# Single_PCB_-_PSK-10D-5.net
KiCad netlist of a schematic drawn in EAGLE
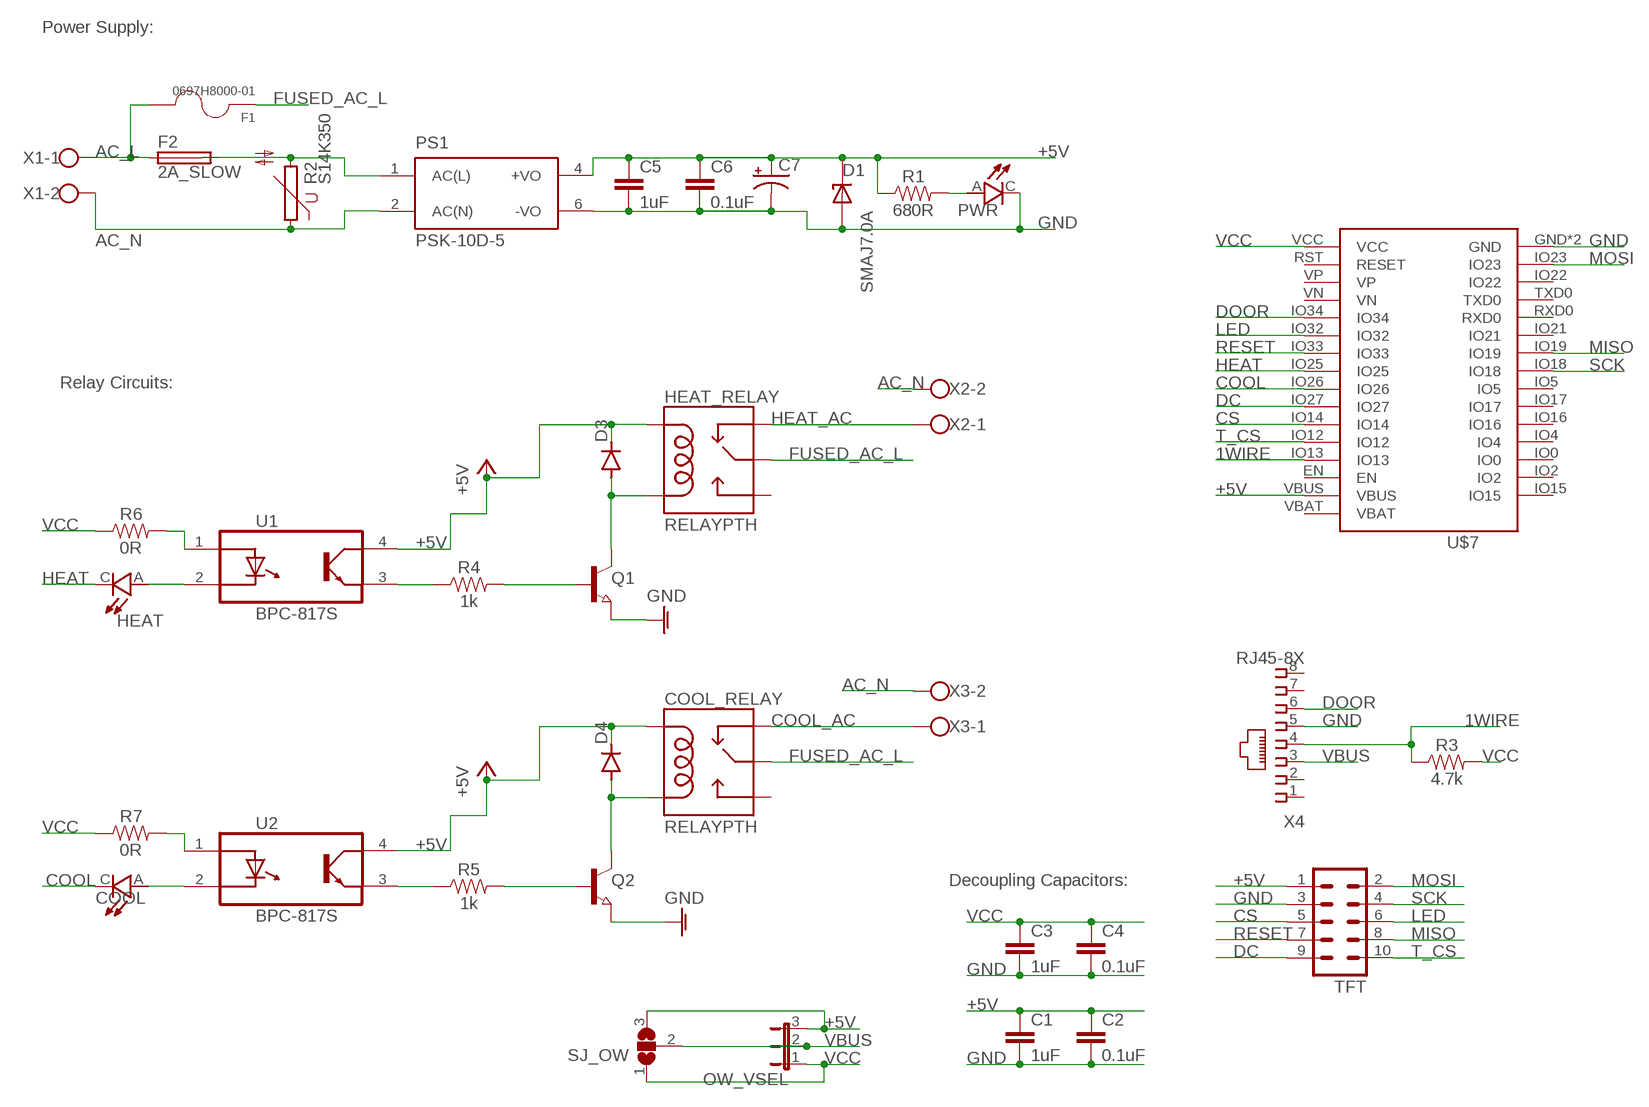
[diagram p0: schematic, sheet 1]

(export (version "E")
  (design (tool "Eeschema 10.0.6"))
  (components
    (comp (ref "C1")
      (value "1uF")
      (footprint "eagle-import:SMD-0805")
      (fields (field (name "LCSC_PART") "C28323"))
      (libsource (lib "eagle-import") (part "CAP_SMD0805"))
    )
    (comp (ref "C2")
      (value "0.1uF")
      (footprint "eagle-import:SMD-0805")
      (fields (field (name "LCSC_PART") "C49678"))
      (libsource (lib "eagle-import") (part "CAP_SMD0805"))
    )
    (comp (ref "C3")
      (value "1uF")
      (footprint "eagle-import:SMD-0805")
      (fields (field (name "LCSC_PART") "C28323"))
      (libsource (lib "eagle-import") (part "CAP_SMD0805"))
    )
    (comp (ref "C4")
      (value "0.1uF")
      (footprint "eagle-import:SMD-0805")
      (fields (field (name "LCSC_PART") "C49678"))
      (libsource (lib "eagle-import") (part "CAP_SMD0805"))
    )
    (comp (ref "C5")
      (value "1uF")
      (footprint "eagle-import:SMD-0805")
      (fields (field (name "LCSC_PART") "C28323"))
      (libsource (lib "eagle-import") (part "CAP_SMD0805"))
    )
    (comp (ref "C6")
      (value "0.1uF")
      (footprint "eagle-import:SMD-0805")
      (fields (field (name "LCSC_PART") "C49678"))
      (libsource (lib "eagle-import") (part "CAP_SMD0805"))
    )
    (comp (ref "C7")
      (value "220uF")
      (footprint "eagle-import:CAPPRD750W80D1600H2700")
      (fields (field (name "LCSC_PART") "C43349"))
      (libsource (lib "eagle-import") (part "220UF-POLAR220UF"))
    )
    (comp (ref "COOL")
      (value "LED_0603LED_SMD_0603")
      (footprint "eagle-import:LED_SMD_0603")
      (fields (field (name "LCSC_PART") "C2286") (field (name "LCSC_PART_1") "C2286"))
      (libsource (lib "eagle-import") (part "LED_0603LED_SMD_0603"))
    )
    (comp (ref "COOL_RELAY")
      (value "RELAYPTH")
      (footprint "eagle-import:SRD-05VDC-SL-C")
      (fields (field (name "LCSC_PART") "C35449"))
      (libsource (lib "eagle-import") (part "RELAYPTH"))
    )
    (comp (ref "D1")
      (value "SMAJ7.0A")
      (footprint "eagle-import:DIOM4325X250N")
      (fields (field (name "MF") "Littelfuse") (field (name "LCSC_PART") "C309904"))
      (libsource (lib "eagle-import") (part "SMAJ7.0A"))
    )
    (comp (ref "D3")
      (value "DIODE-DO214AC")
      (footprint "eagle-import:DO214AC")
      (fields (field (name "LCSC_PART") "C95872"))
      (libsource (lib "eagle-import") (part "DIODE-DO214AC"))
    )
    (comp (ref "D4")
      (value "DIODE-DO214AC")
      (footprint "eagle-import:DO214AC")
      (fields (field (name "LCSC_PART") "C95872"))
      (libsource (lib "eagle-import") (part "DIODE-DO214AC"))
    )
    (comp (ref "F1")
      (value "0697H8000-01")
      (footprint "eagle-import:FUSRR508W60L835T400H810")
      (fields (field (name "MF") "Bel Fuse"))
      (libsource (lib "eagle-import") (part "0697H8000-01"))
    )
    (comp (ref "F2")
      (value "2A_SLOW")
      (footprint "eagle-import:FUSE_BK_PCE-5-R")
      (libsource (lib "eagle-import") (part "FUSEFUSE_85_43"))
    )
    (comp (ref "HEAT")
      (value "LED_0603LED_SMD_0603")
      (footprint "eagle-import:LED_SMD_0603")
      (fields (field (name "LCSC_PART") "C2286") (field (name "LCSC_PART_1") "C2286"))
      (libsource (lib "eagle-import") (part "LED_0603LED_SMD_0603"))
    )
    (comp (ref "HEAT_RELAY")
      (value "RELAYPTH")
      (footprint "eagle-import:SRD-05VDC-SL-C")
      (fields (field (name "LCSC_PART") "C35449"))
      (libsource (lib "eagle-import") (part "RELAYPTH"))
    )
    (comp (ref "OW_VSEL")
      (value "JP2ENOLABEL")
      (footprint "eagle-import:JP2-NOLABEL")
      (libsource (lib "eagle-import") (part "JP2ENOLABEL"))
    )
    (comp (ref "PS1")
      (value "PSK-10D-5")
      (footprint "eagle-import:CONV_PSK-10D-5")
      (fields (field (name "MF") "CUI"))
      (libsource (lib "eagle-import") (part "PSK-10D-5"))
    )
    (comp (ref "PWR")
      (value "LED_0603LED_SMD_0603")
      (footprint "eagle-import:LED_SMD_0603")
      (fields (field (name "LCSC_PART") "C2286") (field (name "LCSC_PART_1") "C2286"))
      (libsource (lib "eagle-import") (part "LED_0603LED_SMD_0603"))
    )
    (comp (ref "Q1")
      (value "NPN-TRANSISTOR_SOT23")
      (footprint "eagle-import:SOT23")
      (libsource (lib "eagle-import") (part "NPN-TRANSISTOR_SOT23"))
    )
    (comp (ref "Q2")
      (value "NPN-TRANSISTOR_SOT23")
      (footprint "eagle-import:SOT23")
      (libsource (lib "eagle-import") (part "NPN-TRANSISTOR_SOT23"))
    )
    (comp (ref "R1")
      (value "680R")
      (footprint "eagle-import:SMD-0805")
      (fields (field (name "LCSC_PART") "C17798"))
      (libsource (lib "eagle-import") (part "RES_SMD0805"))
    )
    (comp (ref "R2")
      (value "S14K350")
      (footprint "eagle-import:S10K350")
      (fields (field (name "LCSC_PART") "C78355"))
      (libsource (lib "eagle-import") (part "S10K350"))
    )
    (comp (ref "R3")
      (value "4.7k")
      (footprint "eagle-import:SMD-0805")
      (fields (field (name "LCSC_PART") "C17673"))
      (libsource (lib "eagle-import") (part "RES_SMD0805"))
    )
    (comp (ref "R4")
      (value "1k")
      (footprint "eagle-import:SMD-0805")
      (fields (field (name "LCSC_PART") "C17513"))
      (libsource (lib "eagle-import") (part "RES_SMD0805"))
    )
    (comp (ref "R5")
      (value "1k")
      (footprint "eagle-import:SMD-0805")
      (fields (field (name "LCSC_PART") "C17513"))
      (libsource (lib "eagle-import") (part "RES_SMD0805"))
    )
    (comp (ref "R6")
      (value "0R")
      (footprint "eagle-import:SMD-0805")
      (fields (field (name "LCSC_PART") "C17477"))
      (libsource (lib "eagle-import") (part "RES_SMD0805"))
    )
    (comp (ref "R7")
      (value "0R")
      (footprint "eagle-import:SMD-0805")
      (fields (field (name "LCSC_PART") "C17477"))
      (libsource (lib "eagle-import") (part "RES_SMD0805"))
    )
    (comp (ref "SJ_OW")
      (value "SJ2W")
      (footprint "eagle-import:SJ_2")
      (libsource (lib "eagle-import") (part "SJ2W"))
    )
    (comp (ref "TFT")
      (value "MA05-2")
      (footprint "eagle-import:MA05-2")
      (libsource (lib "eagle-import") (part "MA05-2"))
    )
    (comp (ref "U$7")
      (value "WEMOS-D32D32_PRO_NO-KEEPOUT")
      (footprint "eagle-import:D32_PRO_NO-KEEPOUT")
      (libsource (lib "eagle-import") (part "WEMOS-D32D32_PRO_NO-KEEPOUT"))
    )
    (comp (ref "U1")
      (value "BPC-817S")
      (footprint "eagle-import:SOIC127P700X210-4N")
      (fields (field (name "LCSC_PART") "C106900"))
      (libsource (lib "eagle-import") (part "BPC-817S"))
    )
    (comp (ref "U2")
      (value "BPC-817S")
      (footprint "eagle-import:SOIC127P700X210-4N")
      (fields (field (name "LCSC_PART") "C106900"))
      (libsource (lib "eagle-import") (part "BPC-817S"))
    )
    (comp (ref "X1")
      (value "W237-102")
      (footprint "eagle-import:W237-102")
      (fields (field (name "MPN") "237-102"))
      (libsource (lib "eagle-import") (part "W237-102"))
    )
    (comp (ref "X2")
      (value "W237-102")
      (footprint "eagle-import:W237-102")
      (fields (field (name "MPN") "237-102"))
      (libsource (lib "eagle-import") (part "W237-102"))
    )
    (comp (ref "X3")
      (value "W237-102")
      (footprint "eagle-import:W237-102")
      (fields (field (name "MPN") "237-102"))
      (libsource (lib "eagle-import") (part "W237-102"))
    )
    (comp (ref "X4")
      (value "RJ45-8X")
      (footprint "eagle-import:RJ45-NO-SHIELD")
      (fields (field (name "LCSC_PART") "C3000197"))
      (libsource (lib "eagle-import") (part "RJ45-8X"))
    )
  )
  (nets
    (net (code "1") (name "+5V") (class "Default")
      (node (ref "C1") (pin "1") (pinfunction "1_1") (pintype "passive"))
      (node (ref "C2") (pin "1") (pinfunction "1_1") (pintype "passive"))
      (node (ref "C5") (pin "1") (pinfunction "1_1") (pintype "passive"))
      (node (ref "C6") (pin "1") (pinfunction "1_1") (pintype "passive"))
      (node (ref "C7") (pin "2") (pinfunction "+_2") (pintype "passive"))
      (node (ref "COOL_RELAY") (pin "COIL1") (pinfunction "COIL1_COIL1") (pintype "bidirectional"))
      (node (ref "D1") (pin "C") (pinfunction "C_C") (pintype "passive"))
      (node (ref "D3") (pin "C") (pinfunction "C_C") (pintype "passive"))
      (node (ref "D4") (pin "C") (pinfunction "C_C") (pintype "passive"))
      (node (ref "HEAT_RELAY") (pin "COIL1") (pinfunction "COIL1_COIL1") (pintype "bidirectional"))
      (node (ref "OW_VSEL") (pin "3") (pinfunction "3_3") (pintype "passive"))
      (node (ref "PS1") (pin "4") (pinfunction "+VO_4") (pintype "output"))
      (node (ref "R1") (pin "1") (pinfunction "1_1") (pintype "passive"))
      (node (ref "SJ_OW") (pin "3") (pinfunction "3_3") (pintype "passive"))
      (node (ref "TFT") (pin "1") (pinfunction "1_1") (pintype "passive"))
      (node (ref "U$7") (pin "VBUS") (pinfunction "VBUS_VBUS") (pintype "bidirectional"))
      (node (ref "U1") (pin "4") (pinfunction "CO_4") (pintype "passive"))
      (node (ref "U2") (pin "4") (pinfunction "CO_4") (pintype "passive"))
    )
    (net (code "2") (name "/1WIRE") (class "Default")
      (node (ref "R3") (pin "1") (pinfunction "1_1") (pintype "passive"))
      (node (ref "U$7") (pin "IO13") (pinfunction "IO13_IO13") (pintype "bidirectional"))
      (node (ref "X4") (pin "4") (pinfunction "4_4") (pintype "passive"))
    )
    (net (code "3") (name "/AC_L") (class "Default")
      (node (ref "F1") (pin "2") (pinfunction "2_2") (pintype "passive"))
      (node (ref "F2") (pin "1") (pinfunction "1_1") (pintype "passive"))
      (node (ref "X1") (pin "1") (pinfunction "KL_1") (pintype "passive"))
    )
    (net (code "4") (name "/AC_N") (class "Default")
      (node (ref "PS1") (pin "2") (pinfunction "AC(N)_2") (pintype "input"))
      (node (ref "R2") (pin "1") (pinfunction "1_1") (pintype "passive"))
      (node (ref "X1") (pin "2") (pinfunction "KL_2") (pintype "passive"))
      (node (ref "X2") (pin "2") (pinfunction "KL_2") (pintype "passive"))
      (node (ref "X3") (pin "2") (pinfunction "KL_2") (pintype "passive"))
    )
    (net (code "5") (name "/COOL") (class "Default")
      (node (ref "COOL") (pin "C") (pinfunction "C_C") (pintype "passive"))
      (node (ref "U$7") (pin "IO26") (pinfunction "IO26_IO26") (pintype "bidirectional"))
    )
    (net (code "6") (name "/COOL_AC") (class "Default")
      (node (ref "COOL_RELAY") (pin "SWCLOSED") (pinfunction "SWCLOSE_SWCLOSED") (pintype "bidirectional"))
      (node (ref "X3") (pin "1") (pinfunction "KL_1") (pintype "passive"))
    )
    (net (code "7") (name "/CS") (class "Default")
      (node (ref "TFT") (pin "5") (pinfunction "5_5") (pintype "passive"))
      (node (ref "U$7") (pin "IO14") (pinfunction "IO14_IO14") (pintype "bidirectional"))
    )
    (net (code "8") (name "/DC") (class "Default")
      (node (ref "TFT") (pin "9") (pinfunction "9_9") (pintype "passive"))
      (node (ref "U$7") (pin "IO27") (pinfunction "IO27_IO27") (pintype "bidirectional"))
    )
    (net (code "9") (name "/DOOR") (class "Default")
      (node (ref "U$7") (pin "IO34") (pinfunction "IO34_IO34") (pintype "bidirectional"))
      (node (ref "X4") (pin "6") (pinfunction "6_6") (pintype "passive"))
    )
    (net (code "10") (name "/FUSED_AC_L") (class "Default")
      (node (ref "COOL_RELAY") (pin "SWCOMMON") (pinfunction "SWCOMMON_SWCOMMON") (pintype "bidirectional"))
      (node (ref "F1") (pin "1") (pinfunction "1_1") (pintype "passive"))
      (node (ref "HEAT_RELAY") (pin "SWCOMMON") (pinfunction "SWCOMMON_SWCOMMON") (pintype "bidirectional"))
    )
    (net (code "11") (name "/HEAT") (class "Default")
      (node (ref "HEAT") (pin "C") (pinfunction "C_C") (pintype "passive"))
      (node (ref "U$7") (pin "IO25") (pinfunction "IO25_IO25") (pintype "bidirectional"))
    )
    (net (code "12") (name "/HEAT_AC") (class "Default")
      (node (ref "HEAT_RELAY") (pin "SWCLOSED") (pinfunction "SWCLOSE_SWCLOSED") (pintype "bidirectional"))
      (node (ref "X2") (pin "1") (pinfunction "KL_1") (pintype "passive"))
    )
    (net (code "13") (name "/LED") (class "Default")
      (node (ref "TFT") (pin "6") (pinfunction "6_6") (pintype "passive"))
      (node (ref "U$7") (pin "IO32") (pinfunction "IO32_IO32") (pintype "bidirectional"))
    )
    (net (code "14") (name "/MISO") (class "Default")
      (node (ref "TFT") (pin "8") (pinfunction "8_8") (pintype "passive"))
      (node (ref "U$7") (pin "IO19") (pinfunction "IO19_IO19") (pintype "bidirectional"))
    )
    (net (code "15") (name "/MOSI") (class "Default")
      (node (ref "TFT") (pin "2") (pinfunction "2_2") (pintype "passive"))
      (node (ref "U$7") (pin "IO23") (pinfunction "IO23_IO23") (pintype "bidirectional"))
    )
    (net (code "16") (name "/RESET") (class "Default")
      (node (ref "TFT") (pin "7") (pinfunction "7_7") (pintype "passive"))
      (node (ref "U$7") (pin "IO33") (pinfunction "IO33_IO33") (pintype "bidirectional"))
    )
    (net (code "17") (name "/SCK") (class "Default")
      (node (ref "TFT") (pin "4") (pinfunction "4_4") (pintype "passive"))
      (node (ref "U$7") (pin "IO18") (pinfunction "IO18_IO18") (pintype "bidirectional"))
    )
    (net (code "18") (name "/T_CS") (class "Default")
      (node (ref "TFT") (pin "10") (pinfunction "10_10") (pintype "passive"))
      (node (ref "U$7") (pin "IO12") (pinfunction "IO12_IO12") (pintype "bidirectional"))
    )
    (net (code "19") (name "/VBUS") (class "Default")
      (node (ref "OW_VSEL") (pin "2") (pinfunction "2_2") (pintype "passive"))
      (node (ref "SJ_OW") (pin "2") (pinfunction "2_2") (pintype "passive"))
      (node (ref "X4") (pin "3") (pinfunction "3_3") (pintype "passive"))
    )
    (net (code "20") (name "/VCC") (class "Default")
      (node (ref "C3") (pin "1") (pinfunction "1_1") (pintype "passive"))
      (node (ref "C4") (pin "1") (pinfunction "1_1") (pintype "passive"))
      (node (ref "OW_VSEL") (pin "1") (pinfunction "1_1") (pintype "passive"))
      (node (ref "R3") (pin "2") (pinfunction "2_2") (pintype "passive"))
      (node (ref "R6") (pin "1") (pinfunction "1_1") (pintype "passive"))
      (node (ref "R7") (pin "1") (pinfunction "1_1") (pintype "passive"))
      (node (ref "SJ_OW") (pin "1") (pinfunction "1_1") (pintype "passive"))
      (node (ref "U$7") (pin "VCC") (pinfunction "VCC_VCC") (pintype "power_in"))
    )
    (net (code "21") (name "GNDA") (class "Default")
      (node (ref "C1") (pin "2") (pinfunction "2_2") (pintype "passive"))
      (node (ref "C2") (pin "2") (pinfunction "2_2") (pintype "passive"))
      (node (ref "C3") (pin "2") (pinfunction "2_2") (pintype "passive"))
      (node (ref "C4") (pin "2") (pinfunction "2_2") (pintype "passive"))
      (node (ref "C5") (pin "2") (pinfunction "2_2") (pintype "passive"))
      (node (ref "C6") (pin "2") (pinfunction "2_2") (pintype "passive"))
      (node (ref "C7") (pin "1") (pinfunction "-_1") (pintype "passive"))
      (node (ref "D1") (pin "A") (pinfunction "A_A") (pintype "passive"))
      (node (ref "PS1") (pin "6") (pinfunction "-VO_6") (pintype "output"))
      (node (ref "PWR") (pin "C") (pinfunction "C_C") (pintype "passive"))
      (node (ref "Q1") (pin "2") (pinfunction "E_2") (pintype "passive"))
      (node (ref "Q2") (pin "2") (pinfunction "E_2") (pintype "passive"))
      (node (ref "TFT") (pin "3") (pinfunction "3_3") (pintype "passive"))
      (node (ref "U$7") (pin "GND") (pinfunction "GND_GND") (pintype "power_in"))
      (node (ref "U$7") (pin "GND2") (pinfunction "GND_GND2") (pintype "power_in"))
      (node (ref "X4") (pin "5") (pinfunction "5_5") (pintype "passive"))
    )
    (net (code "22") (name "Net-(PS1-AC(L))") (class "Default")
      (node (ref "F2") (pin "2") (pinfunction "2_2") (pintype "passive"))
      (node (ref "PS1") (pin "1") (pinfunction "AC(L)_1") (pintype "input"))
      (node (ref "R2") (pin "2") (pinfunction "2_2") (pintype "passive"))
    )
    (net (code "23") (name "Net-(PWR-PadA)") (class "Default")
      (node (ref "PWR") (pin "A") (pinfunction "A_A") (pintype "passive"))
      (node (ref "R1") (pin "2") (pinfunction "2_2") (pintype "passive"))
    )
    (net (code "24") (name "Net-(Q1-B)") (class "Default")
      (node (ref "Q1") (pin "1") (pinfunction "B_1") (pintype "passive"))
      (node (ref "R4") (pin "2") (pinfunction "2_2") (pintype "passive"))
    )
    (net (code "25") (name "Net-(Q1-C)") (class "Default")
      (node (ref "D3") (pin "A") (pinfunction "A_A") (pintype "passive"))
      (node (ref "HEAT_RELAY") (pin "COIL0") (pinfunction "COIL0_COIL0") (pintype "bidirectional"))
      (node (ref "Q1") (pin "3") (pinfunction "C_3") (pintype "passive"))
    )
    (net (code "26") (name "Net-(Q2-B)") (class "Default")
      (node (ref "Q2") (pin "1") (pinfunction "B_1") (pintype "passive"))
      (node (ref "R5") (pin "2") (pinfunction "2_2") (pintype "passive"))
    )
    (net (code "27") (name "Net-(Q2-C)") (class "Default")
      (node (ref "COOL_RELAY") (pin "COIL0") (pinfunction "COIL0_COIL0") (pintype "bidirectional"))
      (node (ref "D4") (pin "A") (pinfunction "A_A") (pintype "passive"))
      (node (ref "Q2") (pin "3") (pinfunction "C_3") (pintype "passive"))
    )
    (net (code "28") (name "Net-(U1-A)") (class "Default")
      (node (ref "R6") (pin "2") (pinfunction "2_2") (pintype "passive"))
      (node (ref "U1") (pin "1") (pinfunction "A_1") (pintype "passive"))
    )
    (net (code "29") (name "Net-(U1-C)") (class "Default")
      (node (ref "HEAT") (pin "A") (pinfunction "A_A") (pintype "passive"))
      (node (ref "U1") (pin "2") (pinfunction "C_2") (pintype "passive"))
    )
    (net (code "30") (name "Net-(U1-E)") (class "Default")
      (node (ref "R4") (pin "1") (pinfunction "1_1") (pintype "passive"))
      (node (ref "U1") (pin "3") (pinfunction "E_3") (pintype "passive"))
    )
    (net (code "31") (name "Net-(U2-A)") (class "Default")
      (node (ref "R7") (pin "2") (pinfunction "2_2") (pintype "passive"))
      (node (ref "U2") (pin "1") (pinfunction "A_1") (pintype "passive"))
    )
    (net (code "32") (name "Net-(U2-C)") (class "Default")
      (node (ref "COOL") (pin "A") (pinfunction "A_A") (pintype "passive"))
      (node (ref "U2") (pin "2") (pinfunction "C_2") (pintype "passive"))
    )
    (net (code "33") (name "Net-(U2-E)") (class "Default")
      (node (ref "R5") (pin "1") (pinfunction "1_1") (pintype "passive"))
      (node (ref "U2") (pin "3") (pinfunction "E_3") (pintype "passive"))
    )
    (net (code "34") (name "unconnected-(COOL_RELAY-PadSWOPEN)") (class "Default")
      (node (ref "COOL_RELAY") (pin "SWOPEN") (pinfunction "SWOPEN_SWOPEN") (pintype "bidirectional"))
    )
    (net (code "35") (name "unconnected-(HEAT_RELAY-PadSWOPEN)") (class "Default")
      (node (ref "HEAT_RELAY") (pin "SWOPEN") (pinfunction "SWOPEN_SWOPEN") (pintype "bidirectional"))
    )
    (net (code "36") (name "unconnected-(U$7-PadEN)") (class "Default")
      (node (ref "U$7") (pin "EN") (pinfunction "EN_EN") (pintype "bidirectional"))
    )
    (net (code "37") (name "unconnected-(U$7-PadIO0)") (class "Default")
      (node (ref "U$7") (pin "IO0") (pinfunction "IO0_IO0") (pintype "bidirectional"))
    )
    (net (code "38") (name "unconnected-(U$7-PadIO2)") (class "Default")
      (node (ref "U$7") (pin "IO2") (pinfunction "IO2_IO2") (pintype "bidirectional"))
    )
    (net (code "39") (name "unconnected-(U$7-PadIO4)") (class "Default")
      (node (ref "U$7") (pin "IO4") (pinfunction "IO4_IO4") (pintype "bidirectional"))
    )
    (net (code "40") (name "unconnected-(U$7-PadIO5)") (class "Default")
      (node (ref "U$7") (pin "IO5") (pinfunction "IO5_IO5") (pintype "bidirectional"))
    )
    (net (code "41") (name "unconnected-(U$7-PadIO15)") (class "Default")
      (node (ref "U$7") (pin "IO15") (pinfunction "IO15_IO15") (pintype "bidirectional"))
    )
    (net (code "42") (name "unconnected-(U$7-PadIO16)") (class "Default")
      (node (ref "U$7") (pin "IO16") (pinfunction "IO16_IO16") (pintype "bidirectional"))
    )
    (net (code "43") (name "unconnected-(U$7-PadIO17)") (class "Default")
      (node (ref "U$7") (pin "IO17") (pinfunction "IO17_IO17") (pintype "bidirectional"))
    )
    (net (code "44") (name "unconnected-(U$7-PadIO21)") (class "Default")
      (node (ref "U$7") (pin "IO21") (pinfunction "IO21_IO21") (pintype "bidirectional"))
    )
    (net (code "45") (name "unconnected-(U$7-PadIO22)") (class "Default")
      (node (ref "U$7") (pin "IO22") (pinfunction "IO22_IO22") (pintype "bidirectional"))
    )
    (net (code "46") (name "unconnected-(U$7-PadRXD0)") (class "Default")
      (node (ref "U$7") (pin "RXD0") (pinfunction "RXD0_RXD0") (pintype "input"))
    )
    (net (code "47") (name "unconnected-(U$7-PadTXD0)") (class "Default")
      (node (ref "U$7") (pin "TXD0") (pinfunction "TXD0_TXD0") (pintype "output"))
    )
    (net (code "48") (name "unconnected-(U$7-PadVBAT)") (class "Default")
      (node (ref "U$7") (pin "VBAT") (pinfunction "VBAT_VBAT") (pintype "bidirectional"))
    )
    (net (code "49") (name "unconnected-(U$7-PadVN)") (class "Default")
      (node (ref "U$7") (pin "VN") (pinfunction "VN_VN") (pintype "bidirectional"))
    )
    (net (code "50") (name "unconnected-(U$7-PadVP)") (class "Default")
      (node (ref "U$7") (pin "VP") (pinfunction "VP_VP") (pintype "bidirectional"))
    )
    (net (code "51") (name "unconnected-(U$7-RESET-PadRST)") (class "Default")
      (node (ref "U$7") (pin "RST") (pinfunction "RESET_RST") (pintype "bidirectional"))
    )
    (net (code "52") (name "unconnected-(X4-Pad1)") (class "Default")
      (node (ref "X4") (pin "1") (pinfunction "1_1") (pintype "passive"))
    )
    (net (code "53") (name "unconnected-(X4-Pad2)") (class "Default")
      (node (ref "X4") (pin "2") (pinfunction "2_2") (pintype "passive"))
    )
    (net (code "54") (name "unconnected-(X4-Pad7)") (class "Default")
      (node (ref "X4") (pin "7") (pinfunction "7_7") (pintype "passive"))
    )
    (net (code "55") (name "unconnected-(X4-Pad8)") (class "Default")
      (node (ref "X4") (pin "8") (pinfunction "8_8") (pintype "passive"))
    )
  )
)
